# PSU_MAX1806_ADJ.net
KiCad netlist of a schematic drawn in Altium Designer
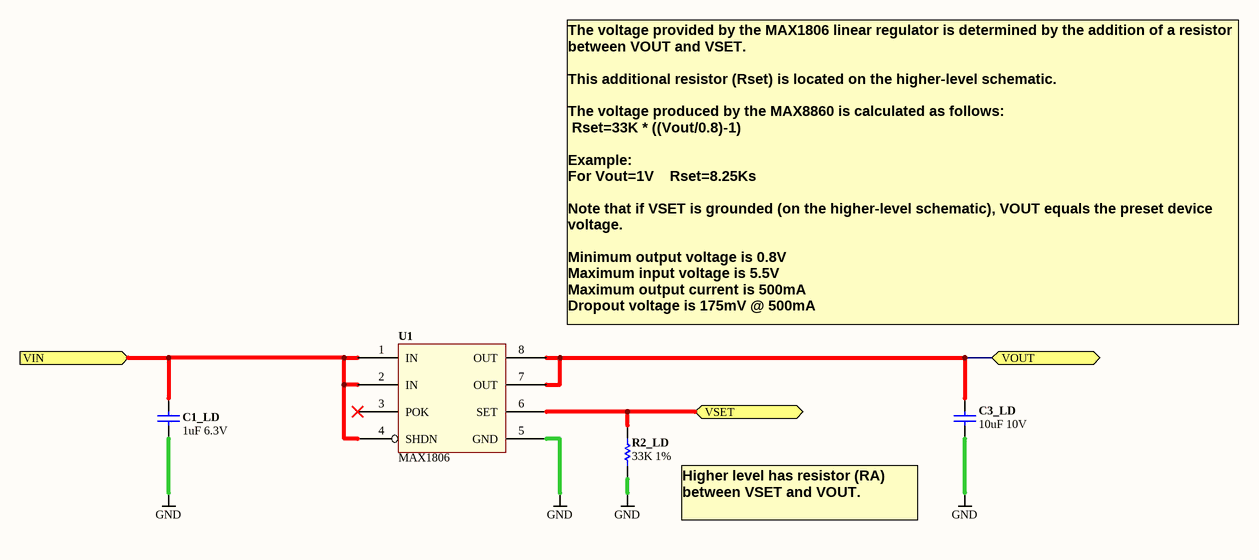
[diagram p0: PSU_MAX1806_ADJ.SchDoc]

(export (version "E")
  (design (tool "Eeschema 10.0.6"))
  (components
    (comp (ref "C1_LD")
      (value "1uF 6.3V")
      (footprint "CAPC1005-STAR")
      (description "Capacitor, Ceramic, 1uF 10% 6.3V 0402 (1005) X5R")
      (fields (field (name "TOLERANCE") "10 %"))
      (libsource (lib "AltiumDesignLibrary") (part "CAP-NP"))
    )
    (comp (ref "C3_LD")
      (value "10uF 10V")
      (footprint "CAPC2012-STAR")
      (description "Capacitor, Ceramic, 10uF 10% 10V 0805 (2012) X5R")
      (fields (field (name "TOLERANCE") "10 %"))
      (libsource (lib "AltiumDesignLibrary") (part "CAP-NP"))
    )
    (comp (ref "R2_LD")
      (value "33K 1%")
      (footprint "RESC1005-STAR")
      (description "Resistor, 33K 1% 0402 (1005)")
      (fields (field (name "TOLERANCE") "1 %"))
      (libsource (lib "AltiumDesignLibrary") (part "RES"))
    )
    (comp (ref "U1")
      (value "MAX1806")
      (footprint "SOP65P490-8")
      (description "MAX1806, 500mA Linear Regulator")
      (libsource (lib "AltiumDesignLibrary") (part "MAX1806"))
    )
  )
  (nets
    (net (code "1") (name "/VIN") (class "Default")
      (node (ref "C1_LD") (pin "1") (pinfunction "1_1") (pintype "passive"))
      (node (ref "U1") (pin "1") (pinfunction "IN_1") (pintype "passive"))
      (node (ref "U1") (pin "2") (pinfunction "IN_2") (pintype "passive"))
      (node (ref "U1") (pin "4") (pinfunction "SHDN_4") (pintype "passive"))
    )
    (net (code "2") (name "/VOUT") (class "Default")
      (node (ref "C3_LD") (pin "1") (pinfunction "1_1") (pintype "passive"))
      (node (ref "U1") (pin "7") (pinfunction "OUT_7") (pintype "passive"))
      (node (ref "U1") (pin "8") (pinfunction "OUT_8") (pintype "passive"))
    )
    (net (code "3") (name "/VSET") (class "Default")
      (node (ref "R2_LD") (pin "1") (pinfunction "1_1") (pintype "passive"))
      (node (ref "U1") (pin "6") (pinfunction "SET_6") (pintype "passive"))
    )
    (net (code "4") (name "GND") (class "Default")
      (node (ref "C1_LD") (pin "2") (pinfunction "2_2") (pintype "passive"))
      (node (ref "C3_LD") (pin "2") (pinfunction "2_2") (pintype "passive"))
      (node (ref "R2_LD") (pin "2") (pinfunction "2_2") (pintype "passive"))
      (node (ref "U1") (pin "5") (pinfunction "GND_5") (pintype "passive"))
    )
    (net (code "5") (name "unconnected-(U1-POK-Pad3)") (class "Default")
      (node (ref "U1") (pin "3") (pinfunction "POK_3") (pintype "passive+no_connect"))
    )
  )
)
